# CAN_TRANSCEIVER.net
KiCad netlist of a schematic drawn in Altium Designer
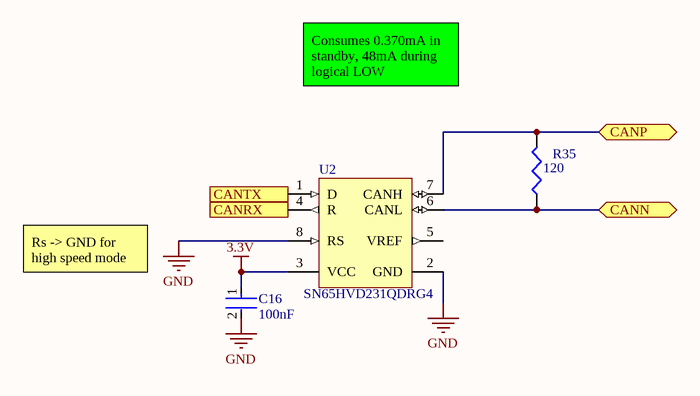
[diagram p0: CAN_TRANSCEIVER.SchDoc]

(export (version "E")
  (design (tool "Eeschema 10.0.6"))
  (components
    (comp (ref "C16")
      (value "100nF")
      (footprint "FP-C0603C-CF-MFG")
      (description "Any 0603 Cap is fine here")
      (fields (field (name "TOLERANCE") "0.1") (field (name "MANUFACTURER") "KEMET"))
      (libsource (lib "Altium Content Vault") (part "b4654b650e69147ec39a6b967a45e02"))
    )
    (comp (ref "R35")
      (value "120")
      (footprint "J1-0603")
      (description "Resistor")
      (fields (field (name "PUBLISHER") "Altium Limited"))
      (libsource (lib "Miscellaneous Devices") (part "Res3"))
    )
    (comp (ref "U2")
      (value "SN65HVD231QDRG4")
      (footprint "D0008A_N")
      (fields (field (name "PARTNUMBER") "SN65HVD231QDRQ1") (field (name "MANUFACTURER") "Texas Instruments"))
      (libsource (lib "Altium Content Vault") (part "TI-SN65HVD231Q-Q1-SOIC_D-8"))
    )
  )
  (nets
    (net (code "1") (name "/CANN") (class "Default")
      (node (ref "R35") (pin "1") (pinfunction "1_1") (pintype "passive"))
      (node (ref "U2") (pin "6") (pinfunction "CANL_6") (pintype "bidirectional"))
    )
    (net (code "2") (name "/CANP") (class "Default")
      (node (ref "R35") (pin "2") (pinfunction "2_2") (pintype "passive"))
      (node (ref "U2") (pin "7") (pinfunction "CANH_7") (pintype "bidirectional"))
    )
    (net (code "3") (name "/CANRX") (class "Default")
      (node (ref "U2") (pin "4") (pinfunction "R_4") (pintype "output"))
    )
    (net (code "4") (name "/CANTX") (class "Default")
      (node (ref "U2") (pin "1") (pinfunction "D_1") (pintype "input"))
    )
    (net (code "5") (name "3.3V") (class "Default")
      (node (ref "C16") (pin "1") (pinfunction "1_1") (pintype "passive"))
      (node (ref "U2") (pin "3") (pinfunction "VCC_3") (pintype "power_in"))
    )
    (net (code "6") (name "GND") (class "Default")
      (node (ref "C16") (pin "2") (pinfunction "2_2") (pintype "passive"))
      (node (ref "U2") (pin "2") (pinfunction "GND_2") (pintype "power_in"))
      (node (ref "U2") (pin "8") (pinfunction "RS_8") (pintype "input"))
    )
    (net (code "7") (name "unconnected-(U2-VREF-Pad5)") (class "Default")
      (node (ref "U2") (pin "5") (pinfunction "VREF_5") (pintype "output"))
    )
  )
)
